# challenge6.net
KiCad netlist of a schematic drawn in EAGLE
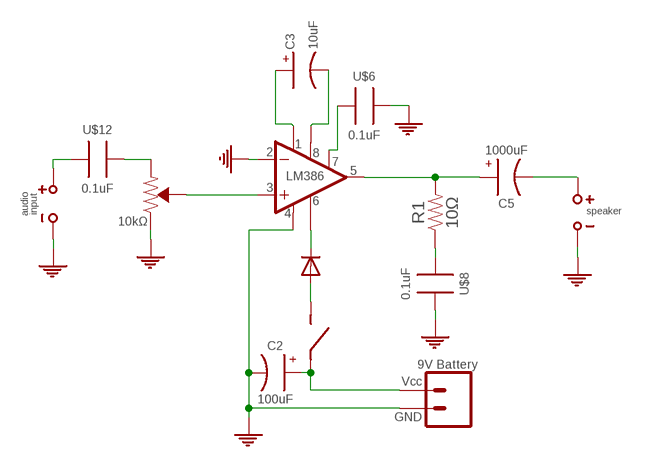
[diagram p0: schematic, sheet 1]

(export (version "E")
  (design (tool "Eeschema 10.0.6"))
  (components
    (comp (ref "IC1")
      (value "LM386")
      (footprint "eagle-import:LM386_DIP08")
      (fields (field (name "MF") "National Semiconductor"))
      (libsource (lib "eagle-import") (part "LM386"))
    )
    (comp (ref "U$1")
      (value "DIODE")
      (footprint "eagle-import:DIODE_1N4001")
      (libsource (lib "eagle-import") (part "DIODE"))
    )
    (comp (ref "U$2")
      (value "SWITCH")
      (footprint "eagle-import:SWITCH")
      (libsource (lib "eagle-import") (part "SWITCH"))
    )
    (comp (ref "U$3")
      (value "C2_100UF")
      (footprint "eagle-import:CAP_100UF_POLARIZED")
      (libsource (lib "eagle-import") (part "C2_100UF"))
    )
    (comp (ref "U$4")
      (value "9V_BATTERY")
      (footprint "eagle-import:9V_BATT")
      (libsource (lib "eagle-import") (part "9V_BATTERY"))
    )
    (comp (ref "U$5")
      (value "C3_10UF")
      (footprint "eagle-import:CAP_10UF_POLARIZED")
      (libsource (lib "eagle-import") (part "C3_10UF"))
    )
    (comp (ref "U$6")
      (value "C_0.1UF")
      (footprint "eagle-import:CAP_0.1UF")
      (libsource (lib "eagle-import") (part "C_0.1UF"))
    )
    (comp (ref "U$7")
      (value "R1_10Ω")
      (footprint "eagle-import:R1_10Ω")
      (libsource (lib "eagle-import") (part "R1_10Ω"))
    )
    (comp (ref "U$8")
      (value "C_0.1UF")
      (footprint "eagle-import:CAP_0.1UF")
      (libsource (lib "eagle-import") (part "C_0.1UF"))
    )
    (comp (ref "U$9")
      (value "C5_1000UF")
      (footprint "eagle-import:CAP_1000UF_POLARIZED")
      (libsource (lib "eagle-import") (part "C5_1000UF"))
    )
    (comp (ref "U$10")
      (value "SPEAKER")
      (footprint "eagle-import:SPEAKER")
      (libsource (lib "eagle-import") (part "SPEAKER"))
    )
    (comp (ref "U$11")
      (value "POTENTIOMETER_10KΩ")
      (footprint "eagle-import:POT_10KΩ")
      (libsource (lib "eagle-import") (part "POTENTIOMETER_10KΩ"))
    )
    (comp (ref "U$12")
      (value "C_0.1UF")
      (footprint "eagle-import:CAP_0.1UF")
      (libsource (lib "eagle-import") (part "C_0.1UF"))
    )
    (comp (ref "U$13")
      (value "AUDIO_INPUT")
      (footprint "eagle-import:AUDIO_INPUT")
      (libsource (lib "eagle-import") (part "AUDIO_INPUT"))
    )
  )
  (nets
    (net (code "1") (name "GND") (class "Default")
      (node (ref "IC1") (pin "2") (pinfunction "-IN_2_2") (pintype "input"))
      (node (ref "IC1") (pin "4") (pinfunction "V-_4_4") (pintype "input"))
      (node (ref "U$10") (pin "-") (pinfunction "-_-") (pintype "passive"))
      (node (ref "U$11") (pin "3") (pinfunction "CW_MINVOL_3") (pintype "passive"))
      (node (ref "U$13") (pin "-") (pinfunction "-_-") (pintype "passive"))
      (node (ref "U$3") (pin "-") (pinfunction "K_-") (pintype "passive"))
      (node (ref "U$4") (pin "-") (pinfunction "-_-") (pintype "passive"))
      (node (ref "U$6") (pin "P$2") (pinfunction "2_P$2") (pintype "passive"))
      (node (ref "U$8") (pin "P$2") (pinfunction "2_P$2") (pintype "passive"))
    )
    (net (code "2") (name "Net-(IC1-+IN_3)") (class "Default")
      (node (ref "IC1") (pin "3") (pinfunction "+IN_3_3") (pintype "input"))
      (node (ref "U$11") (pin "2") (pinfunction "WIPER_2") (pintype "passive"))
    )
    (net (code "3") (name "Net-(IC1-BYPASS_7)") (class "Default")
      (node (ref "IC1") (pin "7") (pinfunction "BYPASS_7_7") (pintype "passive"))
      (node (ref "U$6") (pin "P$1") (pinfunction "1_P$1") (pintype "passive"))
    )
    (net (code "4") (name "Net-(IC1-GAIN1_1)") (class "Default")
      (node (ref "IC1") (pin "1") (pinfunction "GAIN1_1_1") (pintype "passive"))
      (node (ref "U$5") (pin "+") (pinfunction "A_+") (pintype "passive"))
    )
    (net (code "5") (name "Net-(IC1-GAIN2_8)") (class "Default")
      (node (ref "IC1") (pin "8") (pinfunction "GAIN2_8_8") (pintype "passive"))
      (node (ref "U$5") (pin "-") (pinfunction "K_-") (pintype "passive"))
    )
    (net (code "6") (name "Net-(IC1-OUT_5)") (class "Default")
      (node (ref "IC1") (pin "5") (pinfunction "OUT_5_5") (pintype "output"))
      (node (ref "U$7") (pin "2") (pinfunction "2_2") (pintype "passive"))
      (node (ref "U$9") (pin "+") (pinfunction "A_+") (pintype "passive"))
    )
    (net (code "7") (name "Net-(IC1-V+_6)") (class "Default")
      (node (ref "IC1") (pin "6") (pinfunction "V+_6_6") (pintype "input"))
      (node (ref "U$1") (pin "C") (pinfunction "C_C") (pintype "output"))
    )
    (net (code "8") (name "Net-(U$1-PadA)") (class "Default")
      (node (ref "U$1") (pin "A") (pinfunction "A_A") (pintype "input"))
      (node (ref "U$2") (pin "2") (pinfunction "2_2") (pintype "passive"))
    )
    (net (code "9") (name "Net-(U$3-A)") (class "Default")
      (node (ref "U$2") (pin "1") (pinfunction "1_1") (pintype "passive"))
      (node (ref "U$3") (pin "+") (pinfunction "A_+") (pintype "passive"))
      (node (ref "U$4") (pin "+") (pinfunction "+_+") (pintype "passive"))
    )
    (net (code "10") (name "Net-(U$8-1)") (class "Default")
      (node (ref "U$7") (pin "1") (pinfunction "1_1") (pintype "passive"))
      (node (ref "U$8") (pin "P$1") (pinfunction "1_P$1") (pintype "passive"))
    )
    (net (code "11") (name "Net-(U$9-K)") (class "Default")
      (node (ref "U$10") (pin "+") (pinfunction "+_+") (pintype "passive"))
      (node (ref "U$9") (pin "-") (pinfunction "K_-") (pintype "passive"))
    )
    (net (code "12") (name "Net-(U$11-CCW_MAXVOL)") (class "Default")
      (node (ref "U$11") (pin "1") (pinfunction "CCW_MAXVOL_1") (pintype "passive"))
      (node (ref "U$12") (pin "P$2") (pinfunction "2_P$2") (pintype "passive"))
    )
    (net (code "13") (name "Net-(U$12-1)") (class "Default")
      (node (ref "U$12") (pin "P$1") (pinfunction "1_P$1") (pintype "passive"))
      (node (ref "U$13") (pin "+") (pinfunction "+_+") (pintype "passive"))
    )
  )
)
